# nuc977.net
KiCad netlist of a schematic drawn in Altium Designer
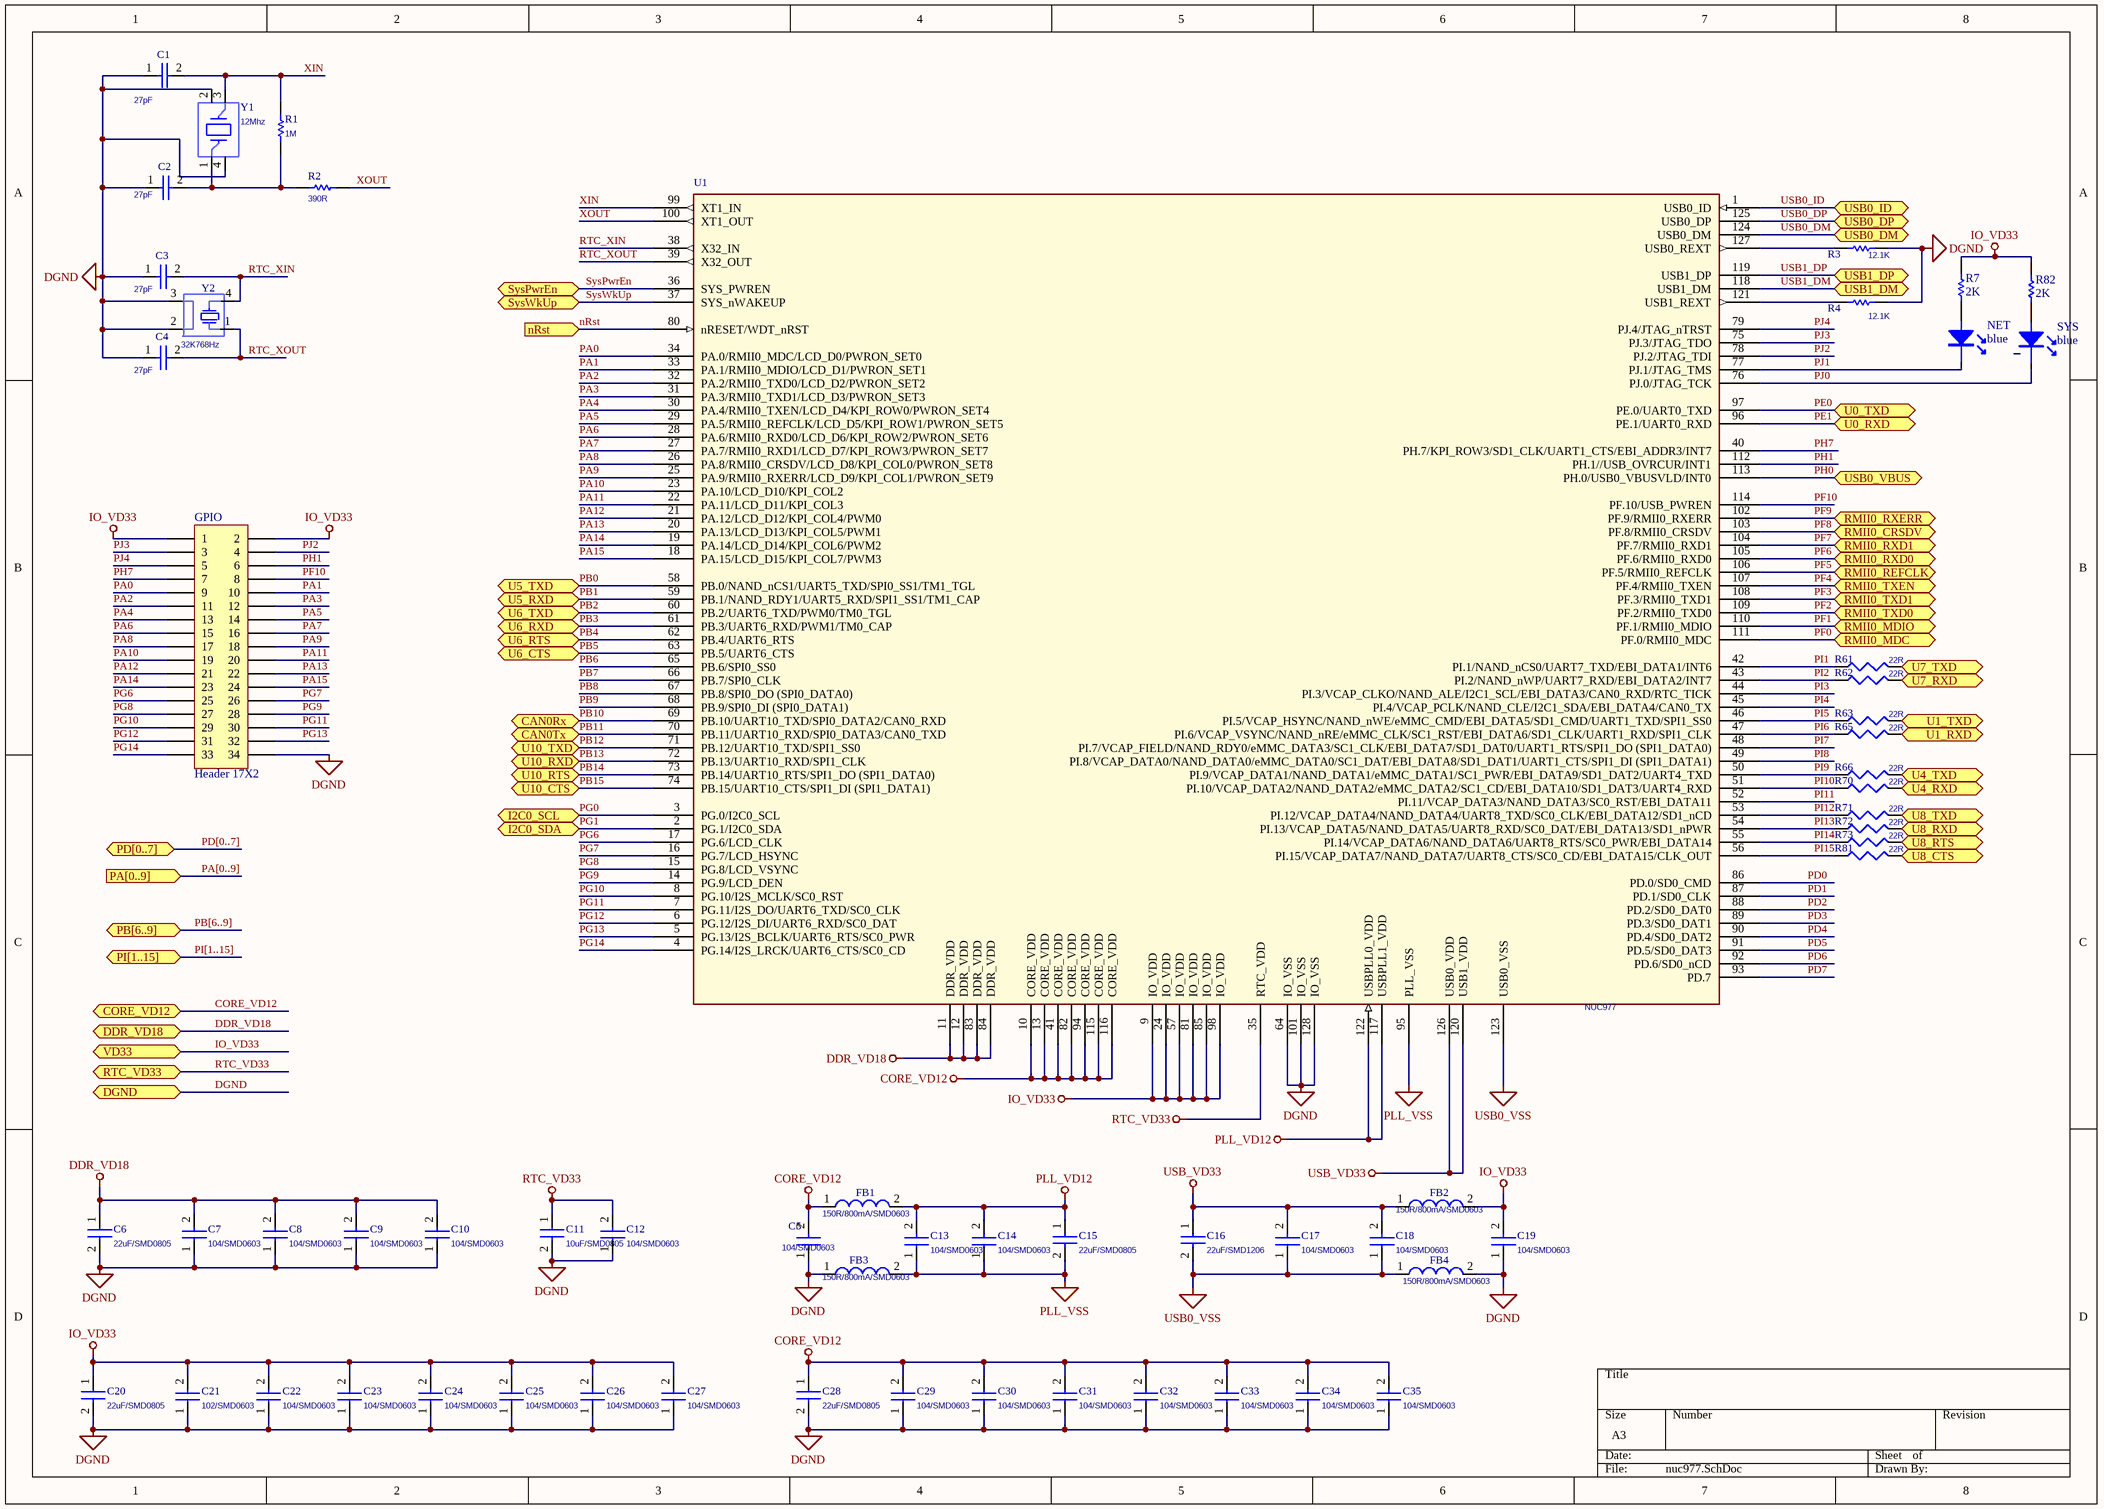
[diagram p0: nuc977.SchDoc]

(export (version "E")
  (design (tool "Eeschema 10.0.6"))
  (components
    (comp (ref "C1")
      (value "27pF")
      (footprint "0603C")
      (description "Capacitor")
      (libsource (lib "MYSTM32") (part "CAP"))
    )
    (comp (ref "C2")
      (value "27pF")
      (footprint "0603C")
      (description "Capacitor")
      (libsource (lib "MYSTM32") (part "CAP"))
    )
    (comp (ref "C3")
      (value "27pF")
      (footprint "0603C")
      (description "Capacitor")
      (libsource (lib "MYSTM32") (part "CAP"))
    )
    (comp (ref "C4")
      (value "27pF")
      (footprint "0603C")
      (description "Capacitor")
      (libsource (lib "MYSTM32") (part "CAP"))
    )
    (comp (ref "C5") (value "104/SMD0603") (footprint "0603C") (libsource (lib "*") (part "C/SMD0603")))
    (comp (ref "C6") (value "22uF/SMD0805") (footprint "C0805") (libsource (lib "*") (part "C/SMD1206")))
    (comp (ref "C7") (value "104/SMD0603") (footprint "0603C") (libsource (lib "*") (part "C/SMD0603")))
    (comp (ref "C8") (value "104/SMD0603") (footprint "0603C") (libsource (lib "*") (part "C/SMD0603")))
    (comp (ref "C9") (value "104/SMD0603") (footprint "0603C") (libsource (lib "*") (part "C/SMD0603")))
    (comp (ref "C10") (value "104/SMD0603") (footprint "0603C") (libsource (lib "*") (part "C/SMD0603")))
    (comp (ref "C11") (value "10uF/SMD0805") (footprint "C0805") (libsource (lib "*") (part "C/SMD0805")))
    (comp (ref "C12") (value "104/SMD0603") (footprint "0603C") (libsource (lib "*") (part "C/SMD0603")))
    (comp (ref "C13") (value "104/SMD0603") (footprint "0603C") (libsource (lib "*") (part "C/SMD0603")))
    (comp (ref "C14") (value "104/SMD0603") (footprint "0603C") (libsource (lib "*") (part "C/SMD0603")))
    (comp (ref "C15") (value "22uF/SMD0805") (footprint "C0805") (libsource (lib "*") (part "C/SMD1206")))
    (comp (ref "C16") (value "22uF/SMD1206") (footprint "C0805") (libsource (lib "*") (part "C/SMD1206")))
    (comp (ref "C17") (value "104/SMD0603") (footprint "0603C") (libsource (lib "*") (part "C/SMD0603")))
    (comp (ref "C18") (value "104/SMD0603") (footprint "0603C") (libsource (lib "*") (part "C/SMD0603")))
    (comp (ref "C19") (value "104/SMD0603") (footprint "0603C") (libsource (lib "*") (part "C/SMD0603")))
    (comp (ref "C20") (value "22uF/SMD0805") (footprint "C0805") (libsource (lib "*") (part "C/SMD1206")))
    (comp (ref "C21") (value "102/SMD0603") (footprint "0603C") (libsource (lib "*") (part "C/SMD0603")))
    (comp (ref "C22") (value "104/SMD0603") (footprint "0603C") (libsource (lib "*") (part "C/SMD0603")))
    (comp (ref "C23") (value "104/SMD0603") (footprint "0603C") (libsource (lib "*") (part "C/SMD0603")))
    (comp (ref "C24") (value "104/SMD0603") (footprint "0603C") (libsource (lib "*") (part "C/SMD0603")))
    (comp (ref "C25") (value "104/SMD0603") (footprint "0603C") (libsource (lib "*") (part "C/SMD0603")))
    (comp (ref "C26") (value "104/SMD0603") (footprint "0603C") (libsource (lib "*") (part "C/SMD0603")))
    (comp (ref "C27") (value "104/SMD0603") (footprint "0603C") (libsource (lib "*") (part "C/SMD0603")))
    (comp (ref "C28") (value "22uF/SMD0805") (footprint "C0805") (libsource (lib "*") (part "C/SMD1206")))
    (comp (ref "C29") (value "104/SMD0603") (footprint "0603C") (libsource (lib "*") (part "C/SMD0603")))
    (comp (ref "C30") (value "104/SMD0603") (footprint "0603C") (libsource (lib "*") (part "C/SMD0603")))
    (comp (ref "C31") (value "104/SMD0603") (footprint "0603C") (libsource (lib "*") (part "C/SMD0603")))
    (comp (ref "C32") (value "104/SMD0603") (footprint "0603C") (libsource (lib "*") (part "C/SMD0603")))
    (comp (ref "C33") (value "104/SMD0603") (footprint "0603C") (libsource (lib "*") (part "C/SMD0603")))
    (comp (ref "C34") (value "104/SMD0603") (footprint "0603C") (libsource (lib "*") (part "C/SMD0603")))
    (comp (ref "C35") (value "104/SMD0603") (footprint "0603C") (libsource (lib "*") (part "C/SMD0603")))
    (comp (ref "FB1")
      (value "150R/800mA/SMD0603")
      (footprint "0603R")
      (libsource (lib "*") (part "FB/SMD0603"))
    )
    (comp (ref "FB2")
      (value "150R/800mA/SMD0603")
      (footprint "0603R")
      (libsource (lib "*") (part "FB/SMD0603"))
    )
    (comp (ref "FB3")
      (value "150R/800mA/SMD0603")
      (footprint "0603R")
      (libsource (lib "*") (part "FB/SMD0603"))
    )
    (comp (ref "FB4")
      (value "150R/800mA/SMD0603")
      (footprint "0603R")
      (libsource (lib "*") (part "FB/SMD0603"))
    )
    (comp (ref "GPIO")
      (value "Header 17X2")
      (footprint "HDR2X17")
      (description "Header, 17-Pin, Dual row")
      (fields (field (name "PUBLISHER") "Altium Limited"))
      (libsource (lib "Miscellaneous Connectors") (part "Header 17X2"))
    )
    (comp (ref "NET") (value "blue") (footprint "LED-0603") (libsource (lib "GT2440原理图库") (part "LED")))
    (comp (ref "R1")
      (value "1M")
      (footprint "0603R")
      (description "Resistor")
      (fields (field (name "PUBLISHER") "Altium Limited"))
      (libsource (lib "STM32F107VCT") (part "res1"))
    )
    (comp (ref "R2")
      (value "390R")
      (footprint "0603R")
      (description "Resistor")
      (fields (field (name "PUBLISHER") "Altium Limited"))
      (libsource (lib "STM32F107VCT") (part "res1"))
    )
    (comp (ref "R3")
      (value "12.1K")
      (footprint "0603R")
      (description "Resistor")
      (fields (field (name "PUBLISHER") "Altium Limited"))
      (libsource (lib "STM32F107VCT") (part "res1"))
    )
    (comp (ref "R4")
      (value "12.1K")
      (footprint "0603R")
      (description "Resistor")
      (fields (field (name "PUBLISHER") "Altium Limited"))
      (libsource (lib "STM32F107VCT") (part "res1"))
    )
    (comp (ref "R7")
      (value "2K")
      (footprint "0603C")
      (description "Resistor")
      (fields (field (name "PUBLISHER") "Altium Limited"))
      (libsource (lib "Miscellaneous Devices") (part "res1"))
    )
    (comp (ref "R61") (value "22R") (footprint "0603R") (libsource (lib "*") (part "R_Dup1")))
    (comp (ref "R62") (value "22R") (footprint "0603R") (libsource (lib "*") (part "R_Dup1")))
    (comp (ref "R63") (value "22R") (footprint "0603R") (libsource (lib "*") (part "R_Dup1")))
    (comp (ref "R65") (value "22R") (footprint "0603R") (libsource (lib "*") (part "R_Dup1")))
    (comp (ref "R66") (value "22R") (footprint "0603R") (libsource (lib "*") (part "R_Dup1")))
    (comp (ref "R70") (value "22R") (footprint "0603R") (libsource (lib "*") (part "R_Dup1")))
    (comp (ref "R71") (value "22R") (footprint "0603R") (libsource (lib "*") (part "R_Dup1")))
    (comp (ref "R72") (value "22R") (footprint "0603R") (libsource (lib "*") (part "R_Dup1")))
    (comp (ref "R73") (value "22R") (footprint "0603R") (libsource (lib "*") (part "R_Dup1")))
    (comp (ref "R81") (value "22R") (footprint "0603R") (libsource (lib "*") (part "R_Dup1")))
    (comp (ref "R82")
      (value "2K")
      (footprint "0603C")
      (description "Resistor")
      (fields (field (name "PUBLISHER") "Altium Limited"))
      (libsource (lib "Miscellaneous Devices") (part "res1"))
    )
    (comp (ref "SYS") (value "blue") (footprint "LED-0603") (libsource (lib "GT2440原理图库") (part "LED")))
    (comp (ref "U1") (value "NUC977") (footprint "QFP128/16/0.4") (libsource (lib "*") (part "NUC977_7")))
    (comp (ref "Y1") (value "12Mhz") (footprint "HCX-3SB3225") (libsource (lib "changyong") (part "12Mhz")))
    (comp (ref "Y2") (value "32K768Hz") (footprint "32K768Hz") (libsource (lib "n32905") (part "32K768Hz")))
  )
  (nets
    (net (code "1") (name "/PA0") (class "Default")
      (node (ref "GPIO") (pin "9") (pinfunction "9_9") (pintype "passive"))
      (node (ref "U1") (pin "34") (pinfunction "PA.0/RMII0_MDC/LCD_D0/PWRON_SET0_34") (pintype "passive"))
    )
    (net (code "2") (name "/PA1") (class "Default")
      (node (ref "GPIO") (pin "10") (pinfunction "10_10") (pintype "passive"))
      (node (ref "U1") (pin "33") (pinfunction "PA.1/RMII0_MDIO/LCD_D1/PWRON_SET1_33") (pintype "passive"))
    )
    (net (code "3") (name "/PA2") (class "Default")
      (node (ref "GPIO") (pin "11") (pinfunction "11_11") (pintype "passive"))
      (node (ref "U1") (pin "32") (pinfunction "PA.2/RMII0_TXD0/LCD_D2/PWRON_SET2_32") (pintype "passive"))
    )
    (net (code "4") (name "/PA3") (class "Default")
      (node (ref "GPIO") (pin "12") (pinfunction "12_12") (pintype "passive"))
      (node (ref "U1") (pin "31") (pinfunction "PA.3/RMII0_TXD1/LCD_D3/PWRON_SET3_31") (pintype "passive"))
    )
    (net (code "5") (name "/PA4") (class "Default")
      (node (ref "GPIO") (pin "13") (pinfunction "13_13") (pintype "passive"))
      (node (ref "U1") (pin "30") (pinfunction "PA.4/RMII0_TXEN/LCD_D4/KPI_ROW0/PWRON_SET4_30") (pintype "passive"))
    )
    (net (code "6") (name "/PA5") (class "Default")
      (node (ref "GPIO") (pin "14") (pinfunction "14_14") (pintype "passive"))
      (node (ref "U1") (pin "29") (pinfunction "PA.5/RMII0_REFCLK/LCD_D5/KPI_ROW1/PWRON_SET5_29") (pintype "passive"))
    )
    (net (code "7") (name "/PA6") (class "Default")
      (node (ref "GPIO") (pin "15") (pinfunction "15_15") (pintype "passive"))
      (node (ref "U1") (pin "28") (pinfunction "PA.6/RMII0_RXD0/LCD_D6/KPI_ROW2/PWRON_SET6_28") (pintype "passive"))
    )
    (net (code "8") (name "/PA7") (class "Default")
      (node (ref "GPIO") (pin "16") (pinfunction "16_16") (pintype "passive"))
      (node (ref "U1") (pin "27") (pinfunction "PA.7/RMII0_RXD1/LCD_D7/KPI_ROW3/PWRON_SET7_27") (pintype "passive"))
    )
    (net (code "9") (name "/PA8") (class "Default")
      (node (ref "GPIO") (pin "17") (pinfunction "17_17") (pintype "passive"))
      (node (ref "U1") (pin "26") (pinfunction "PA.8/RMII0_CRSDV/LCD_D8/KPI_COL0/PWRON_SET8_26") (pintype "passive"))
    )
    (net (code "10") (name "/PA9") (class "Default")
      (node (ref "GPIO") (pin "18") (pinfunction "18_18") (pintype "passive"))
      (node (ref "U1") (pin "25") (pinfunction "PA.9/RMII0_RXERR/LCD_D9/KPI_COL1/PWRON_SET9_25") (pintype "passive"))
    )
    (net (code "11") (name "/PA10") (class "Default")
      (node (ref "GPIO") (pin "19") (pinfunction "19_19") (pintype "passive"))
      (node (ref "U1") (pin "23") (pinfunction "PA.10/LCD_D10/KPI_COL2_23") (pintype "passive"))
    )
    (net (code "12") (name "/PA11") (class "Default")
      (node (ref "GPIO") (pin "20") (pinfunction "20_20") (pintype "passive"))
      (node (ref "U1") (pin "22") (pinfunction "PA.11/LCD_D11/KPI_COL3_22") (pintype "passive"))
    )
    (net (code "13") (name "/PA12") (class "Default")
      (node (ref "GPIO") (pin "21") (pinfunction "21_21") (pintype "passive"))
      (node (ref "U1") (pin "21") (pinfunction "PA.12/LCD_D12/KPI_COL4/PWM0_21") (pintype "passive"))
    )
    (net (code "14") (name "/PA13") (class "Default")
      (node (ref "GPIO") (pin "22") (pinfunction "22_22") (pintype "passive"))
      (node (ref "U1") (pin "20") (pinfunction "PA.13/LCD_D13/KPI_COL5/PWM1_20") (pintype "passive"))
    )
    (net (code "15") (name "/PA14") (class "Default")
      (node (ref "GPIO") (pin "23") (pinfunction "23_23") (pintype "passive"))
      (node (ref "U1") (pin "19") (pinfunction "PA.14/LCD_D14/KPI_COL6/PWM2_19") (pintype "passive"))
    )
    (net (code "16") (name "/PA15") (class "Default")
      (node (ref "GPIO") (pin "24") (pinfunction "24_24") (pintype "passive"))
      (node (ref "U1") (pin "18") (pinfunction "PA.15/LCD_D15/KPI_COL7/PWM3_18") (pintype "passive"))
    )
    (net (code "18") (name "/PB0") (class "Default")
      (node (ref "U1") (pin "58") (pinfunction "PB.0/NAND_nCS1/UART5_TXD/SPI0_SS1/TM1_TGL_58") (pintype "passive"))
    )
    (net (code "19") (name "/PB1") (class "Default")
      (node (ref "U1") (pin "59") (pinfunction "PB.1/NAND_RDY1/UART5_RXD/SPI1_SS1/TM1_CAP_59") (pintype "passive"))
    )
    (net (code "20") (name "/PB2") (class "Default")
      (node (ref "U1") (pin "60") (pinfunction "PB.2/UART6_TXD/PWM0/TM0_TGL_60") (pintype "passive"))
    )
    (net (code "21") (name "/PB3") (class "Default")
      (node (ref "U1") (pin "61") (pinfunction "PB.3/UART6_RXD/PWM1/TM0_CAP_61") (pintype "passive"))
    )
    (net (code "22") (name "/PB4") (class "Default")
      (node (ref "U1") (pin "62") (pinfunction "PB.4/UART6_RTS_62") (pintype "passive"))
    )
    (net (code "23") (name "/PB5") (class "Default")
      (node (ref "U1") (pin "63") (pinfunction "PB.5/UART6_CTS_63") (pintype "passive"))
    )
    (net (code "24") (name "/PB6") (class "Default")
      (node (ref "U1") (pin "65") (pinfunction "PB.6/SPI0_SS0_65") (pintype "passive"))
    )
    (net (code "25") (name "/PB7") (class "Default")
      (node (ref "U1") (pin "66") (pinfunction "PB.7/SPI0_CLK_66") (pintype "passive"))
    )
    (net (code "26") (name "/PB8") (class "Default")
      (node (ref "U1") (pin "67") (pinfunction "PB.8/SPI0_DO_(SPI0_DATA0)_67") (pintype "passive"))
    )
    (net (code "27") (name "/PB9") (class "Default")
      (node (ref "U1") (pin "68") (pinfunction "PB.9/SPI0_DI_(SPI0_DATA1)_68") (pintype "passive"))
    )
    (net (code "28") (name "/PB10") (class "Default")
      (node (ref "U1") (pin "69") (pinfunction "PB.10/UART10_TXD/SPI0_DATA2/CAN0_RXD_69") (pintype "passive"))
    )
    (net (code "29") (name "/PB11") (class "Default")
      (node (ref "U1") (pin "70") (pinfunction "PB.11/UART10_RXD/SPI0_DATA3/CAN0_TXD_70") (pintype "passive"))
    )
    (net (code "30") (name "/PB12") (class "Default")
      (node (ref "U1") (pin "71") (pinfunction "PB.12/UART10_TXD/SPI1_SS0_71") (pintype "passive"))
    )
    (net (code "31") (name "/PB13") (class "Default")
      (node (ref "U1") (pin "72") (pinfunction "PB.13/UART10_RXD/SPI1_CLK_72") (pintype "passive"))
    )
    (net (code "32") (name "/PB14") (class "Default")
      (node (ref "U1") (pin "73") (pinfunction "PB.14/UART10_RTS/SPI1_DO_(SPI1_DATA0)_73") (pintype "passive"))
    )
    (net (code "33") (name "/PB15") (class "Default")
      (node (ref "U1") (pin "74") (pinfunction "PB.15/UART10_CTS/SPI1_DI_(SPI1_DATA1)_74") (pintype "passive"))
    )
    (net (code "35") (name "/PD0") (class "Default")
      (node (ref "U1") (pin "86") (pinfunction "PD.0/SD0_CMD_86") (pintype "passive"))
    )
    (net (code "36") (name "/PD1") (class "Default")
      (node (ref "U1") (pin "87") (pinfunction "PD.1/SD0_CLK_87") (pintype "passive"))
    )
    (net (code "37") (name "/PD2") (class "Default")
      (node (ref "U1") (pin "88") (pinfunction "PD.2/SD0_DAT0_88") (pintype "passive"))
    )
    (net (code "38") (name "/PD3") (class "Default")
      (node (ref "U1") (pin "89") (pinfunction "PD.3/SD0_DAT1_89") (pintype "passive"))
    )
    (net (code "39") (name "/PD4") (class "Default")
      (node (ref "U1") (pin "90") (pinfunction "PD.4/SD0_DAT2_90") (pintype "passive"))
    )
    (net (code "40") (name "/PD5") (class "Default")
      (node (ref "U1") (pin "91") (pinfunction "PD.5/SD0_DAT3_91") (pintype "passive"))
    )
    (net (code "41") (name "/PD6") (class "Default")
      (node (ref "U1") (pin "92") (pinfunction "PD.6/SD0_nCD_92") (pintype "passive"))
    )
    (net (code "42") (name "/PD7") (class "Default")
      (node (ref "U1") (pin "93") (pinfunction "PD.7_93") (pintype "passive"))
    )
    (net (code "44") (name "/PE0") (class "Default")
      (node (ref "U1") (pin "97") (pinfunction "PE.0/UART0_TXD_97") (pintype "passive"))
    )
    (net (code "45") (name "/PE1") (class "Default")
      (node (ref "U1") (pin "96") (pinfunction "PE.1/UART0_RXD_96") (pintype "passive"))
    )
    (net (code "46") (name "/PF0") (class "Default")
      (node (ref "U1") (pin "111") (pinfunction "PF.0/RMII0_MDC_111") (pintype "passive"))
    )
    (net (code "47") (name "/PF1") (class "Default")
      (node (ref "U1") (pin "110") (pinfunction "PF.1/RMII0_MDIO_110") (pintype "passive"))
    )
    (net (code "48") (name "/PF2") (class "Default")
      (node (ref "U1") (pin "109") (pinfunction "PF.2/RMII0_TXD0_109") (pintype "passive"))
    )
    (net (code "49") (name "/PF3") (class "Default")
      (node (ref "U1") (pin "108") (pinfunction "PF.3/RMII0_TXD1_108") (pintype "passive"))
    )
    (net (code "50") (name "/PF4") (class "Default")
      (node (ref "U1") (pin "107") (pinfunction "PF.4/RMII0_TXEN_107") (pintype "passive"))
    )
    (net (code "51") (name "/PF5") (class "Default")
      (node (ref "U1") (pin "106") (pinfunction "PF.5/RMII0_REFCLK_106") (pintype "passive"))
    )
    (net (code "52") (name "/PF6") (class "Default")
      (node (ref "U1") (pin "105") (pinfunction "PF.6/RMII0_RXD0_105") (pintype "passive"))
    )
    (net (code "53") (name "/PF7") (class "Default")
      (node (ref "U1") (pin "104") (pinfunction "PF.7/RMII0_RXD1_104") (pintype "passive"))
    )
    (net (code "54") (name "/PF8") (class "Default")
      (node (ref "U1") (pin "103") (pinfunction "PF.8/RMII0_CRSDV_103") (pintype "passive"))
    )
    (net (code "55") (name "/PF9") (class "Default")
      (node (ref "U1") (pin "102") (pinfunction "PF.9/RMII0_RXERR_102") (pintype "passive"))
    )
    (net (code "56") (name "/PF10") (class "Default")
      (node (ref "GPIO") (pin "8") (pinfunction "8_8") (pintype "passive"))
      (node (ref "U1") (pin "114") (pinfunction "PF.10/USB_PWREN_114") (pintype "passive"))
    )
    (net (code "57") (name "/PG0") (class "Default")
      (node (ref "U1") (pin "3") (pinfunction "PG.0/I2C0_SCL_3") (pintype "passive"))
    )
    (net (code "58") (name "/PG1") (class "Default")
      (node (ref "U1") (pin "2") (pinfunction "PG.1/I2C0_SDA_2") (pintype "passive"))
    )
    (net (code "59") (name "/PG6") (class "Default")
      (node (ref "GPIO") (pin "25") (pinfunction "25_25") (pintype "passive"))
      (node (ref "U1") (pin "17") (pinfunction "PG.6/LCD_CLK_17") (pintype "passive"))
    )
    (net (code "60") (name "/PG7") (class "Default")
      (node (ref "GPIO") (pin "26") (pinfunction "26_26") (pintype "passive"))
      (node (ref "U1") (pin "16") (pinfunction "PG.7/LCD_HSYNC_16") (pintype "passive"))
    )
    (net (code "61") (name "/PG8") (class "Default")
      (node (ref "GPIO") (pin "27") (pinfunction "27_27") (pintype "passive"))
      (node (ref "U1") (pin "15") (pinfunction "PG.8/LCD_VSYNC_15") (pintype "passive"))
    )
    (net (code "62") (name "/PG9") (class "Default")
      (node (ref "GPIO") (pin "28") (pinfunction "28_28") (pintype "passive"))
      (node (ref "U1") (pin "14") (pinfunction "PG.9/LCD_DEN_14") (pintype "passive"))
    )
    (net (code "63") (name "/PG10") (class "Default")
      (node (ref "GPIO") (pin "29") (pinfunction "29_29") (pintype "passive"))
      (node (ref "U1") (pin "8") (pinfunction "PG.10/I2S_MCLK/SC0_RST_8") (pintype "passive"))
    )
    (net (code "64") (name "/PG11") (class "Default")
      (node (ref "GPIO") (pin "30") (pinfunction "30_30") (pintype "passive"))
      (node (ref "U1") (pin "7") (pinfunction "PG.11/I2S_DO/UART6_TXD/SC0_CLK_7") (pintype "passive"))
    )
    (net (code "65") (name "/PG12") (class "Default")
      (node (ref "GPIO") (pin "31") (pinfunction "31_31") (pintype "passive"))
      (node (ref "U1") (pin "6") (pinfunction "PG.12/I2S_DI/UART6_RXD/SC0_DAT_6") (pintype "passive"))
    )
    (net (code "66") (name "/PG13") (class "Default")
      (node (ref "GPIO") (pin "32") (pinfunction "32_32") (pintype "passive"))
      (node (ref "U1") (pin "5") (pinfunction "PG.13/I2S_BCLK/UART6_RTS/SC0_PWR_5") (pintype "passive"))
    )
    (net (code "67") (name "/PG14") (class "Default")
      (node (ref "GPIO") (pin "33") (pinfunction "33_33") (pintype "passive"))
      (node (ref "U1") (pin "4") (pinfunction "PG.14/I2S_LRCK/UART6_CTS/SC0_CD_4") (pintype "passive"))
    )
    (net (code "68") (name "/PH0") (class "Default")
      (node (ref "U1") (pin "113") (pinfunction "PH.0/USB0_VBUSVLD/INT0_113") (pintype "passive"))
    )
    (net (code "69") (name "/PH1") (class "Default")
      (node (ref "GPIO") (pin "6") (pinfunction "6_6") (pintype "passive"))
      (node (ref "U1") (pin "112") (pinfunction "PH.1//USB_OVRCUR/INT1_112") (pintype "passive"))
    )
    (net (code "70") (name "/PH7") (class "Default")
      (node (ref "GPIO") (pin "7") (pinfunction "7_7") (pintype "passive"))
      (node (ref "U1") (pin "40") (pinfunction "PH.7/KPI_ROW3/SD1_CLK/UART1_CTS/EBI_ADDR3/INT7_40") (pintype "passive"))
    )
    (net (code "71") (name "/PI1") (class "Default")
      (node (ref "R61") (pin "1") (pinfunction "1_1") (pintype "passive"))
      (node (ref "U1") (pin "42") (pinfunction "PI.1/NAND_nCS0/UART7_TXD/EBI_DATA1/INT6_42") (pintype "passive"))
    )
    (net (code "72") (name "/PI2") (class "Default")
      (node (ref "R62") (pin "1") (pinfunction "1_1") (pintype "passive"))
      (node (ref "U1") (pin "43") (pinfunction "PI.2/NAND_nWP/UART7_RXD/EBI_DATA2/INT7_43") (pintype "passive"))
    )
    (net (code "73") (name "/PI3") (class "Default")
      (node (ref "U1") (pin "44") (pinfunction "PI.3/VCAP_CLKO/NAND_ALE/I2C1_SCL/EBI_DATA3/CAN0_RXD/RTC_TICK_44") (pintype "passive"))
    )
    (net (code "74") (name "/PI4") (class "Default")
      (node (ref "U1") (pin "45") (pinfunction "PI.4/VCAP_PCLK/NAND_CLE/I2C1_SDA/EBI_DATA4/CAN0_TX_45") (pintype "passive"))
    )
    (net (code "75") (name "/PI5") (class "Default")
      (node (ref "R63") (pin "1") (pinfunction "1_1") (pintype "passive"))
      (node (ref "U1") (pin "46") (pinfunction "PI.5/VCAP_HSYNC/NAND_nWE/eMMC_CMD/EBI_DATA5/SD1_CMD/UART1_TXD/SPI1_SS0_46") (pintype "passive"))
    )
    (net (code "76") (name "/PI6") (class "Default")
      (node (ref "R65") (pin "1") (pinfunction "1_1") (pintype "passive"))
      (node (ref "U1") (pin "47") (pinfunction "PI.6/VCAP_VSYNC/NAND_nRE/eMMC_CLK/SC1_RST/EBI_DATA6/SD1_CLK/UART1_RXD/SPI1_CLK_47") (pintype "passive"))
    )
    (net (code "77") (name "/PI7") (class "Default")
      (node (ref "U1") (pin "48") (pinfunction "PI.7/VCAP_FIELD/NAND_RDY0/eMMC_DATA3/SC1_CLK/EBI_DATA7/SD1_DAT0/UART1_RTS/SPI1_DO_(SPI1_DATA0)_48") (pintype "passive"))
    )
    (net (code "78") (name "/PI8") (class "Default")
      (node (ref "U1") (pin "49") (pinfunction "PI.8/VCAP_DATA0/NAND_DATA0/eMMC_DATA0/SC1_DAT/EBI_DATA8/SD1_DAT1/UART1_CTS/SPI1_DI_(SPI1_DATA1)_49") (pintype "passive"))
    )
    (net (code "79") (name "/PI9") (class "Default")
      (node (ref "R66") (pin "1") (pinfunction "1_1") (pintype "passive"))
      (node (ref "U1") (pin "50") (pinfunction "PI.9/VCAP_DATA1/NAND_DATA1/eMMC_DATA1/SC1_PWR/EBI_DATA9/SD1_DAT2/UART4_TXD_50") (pintype "passive"))
    )
    (net (code "80") (name "/PI10") (class "Default")
      (node (ref "R70") (pin "1") (pinfunction "1_1") (pintype "passive"))
      (node (ref "U1") (pin "51") (pinfunction "PI.10/VCAP_DATA2/NAND_DATA2/eMMC_DATA2/SC1_CD/EBI_DATA10/SD1_DAT3/UART4_RXD_51") (pintype "passive"))
    )
    (net (code "81") (name "/PI11") (class "Default")
      (node (ref "U1") (pin "52") (pinfunction "PI.11/VCAP_DATA3/NAND_DATA3/SC0_RST/EBI_DATA11_52") (pintype "passive"))
    )
    (net (code "82") (name "/PI12") (class "Default")
      (node (ref "R71") (pin "1") (pinfunction "1_1") (pintype "passive"))
      (node (ref "U1") (pin "53") (pinfunction "PI.12/VCAP_DATA4/NAND_DATA4/UART8_TXD/SC0_CLK/EBI_DATA12/SD1_nCD_53") (pintype "passive"))
    )
    (net (code "83") (name "/PI13") (class "Default")
      (node (ref "R72") (pin "1") (pinfunction "1_1") (pintype "passive"))
      (node (ref "U1") (pin "54") (pinfunction "PI.13/VCAP_DATA5/NAND_DATA5/UART8_RXD/SC0_DAT/EBI_DATA13/SD1_nPWR_54") (pintype "passive"))
    )
    (net (code "84") (name "/PI14") (class "Default")
      (node (ref "R73") (pin "1") (pinfunction "1_1") (pintype "passive"))
      (node (ref "U1") (pin "55") (pinfunction "PI.14/VCAP_DATA6/NAND_DATA6/UART8_RTS/SC0_PWR/EBI_DATA14_55") (pintype "passive"))
    )
    (net (code "85") (name "/PI15") (class "Default")
      (node (ref "R81") (pin "1") (pinfunction "1_1") (pintype "passive"))
      (node (ref "U1") (pin "56") (pinfunction "PI.15/VCAP_DATA7/NAND_DATA7/UART8_CTS/SC0_CD/EBI_DATA15/CLK_OUT_56") (pintype "passive"))
    )
    (net (code "87") (name "/PJ0") (class "Default")
      (node (ref "SYS") (pin "2") (pinfunction "2_2") (pintype "passive"))
      (node (ref "U1") (pin "76") (pinfunction "PJ.0/JTAG_TCK_76") (pintype "passive"))
    )
    (net (code "88") (name "/PJ1") (class "Default")
      (node (ref "NET") (pin "2") (pinfunction "2_2") (pintype "passive"))
      (node (ref "U1") (pin "77") (pinfunction "PJ.1/JTAG_TMS_77") (pintype "passive"))
    )
    (net (code "89") (name "/PJ2") (class "Default")
      (node (ref "GPIO") (pin "4") (pinfunction "4_4") (pintype "passive"))
      (node (ref "U1") (pin "78") (pinfunction "PJ.2/JTAG_TDI_78") (pintype "passive"))
    )
    (net (code "90") (name "/PJ3") (class "Default")
      (node (ref "GPIO") (pin "3") (pinfunction "3_3") (pintype "passive"))
      (node (ref "U1") (pin "75") (pinfunction "PJ.3/JTAG_TDO_75") (pintype "passive"))
    )
    (net (code "91") (name "/PJ4") (class "Default")
      (node (ref "GPIO") (pin "5") (pinfunction "5_5") (pintype "passive"))
      (node (ref "U1") (pin "79") (pinfunction "PJ.4/JTAG_nTRST_79") (pintype "passive"))
    )
    (net (code "92") (name "/RTC_XIN") (class "Default")
      (node (ref "C3") (pin "2") (pinfunction "2_2") (pintype "passive"))
      (node (ref "U1") (pin "38") (pinfunction "X32_IN_38") (pintype "output"))
      (node (ref "Y2") (pin "4") (pinfunction "4_4") (pintype "passive"))
    )
    (net (code "93") (name "/RTC_XOUT") (class "Default")
      (node (ref "C4") (pin "2") (pinfunction "2_2") (pintype "passive"))
      (node (ref "U1") (pin "39") (pinfunction "X32_OUT_39") (pintype "output"))
      (node (ref "Y2") (pin "1") (pinfunction "1_1") (pintype "passive"))
    )
    (net (code "94") (name "/SysPwrEn") (class "Default")
      (node (ref "U1") (pin "36") (pinfunction "SYS_PWREN_36") (pintype "passive"))
    )
    (net (code "95") (name "/SysWkUp") (class "Default")
      (node (ref "U1") (pin "37") (pinfunction "SYS_nWAKEUP_37") (pintype "passive"))
    )
    (net (code "96") (name "/U1_RXD") (class "Default")
      (node (ref "R65") (pin "2") (pinfunction "2_2") (pintype "passive"))
    )
    (net (code "97") (name "/U1_TXD") (class "Default")
      (node (ref "R63") (pin "2") (pinfunction "2_2") (pintype "passive"))
    )
    (net (code "98") (name "/U4_RXD") (class "Default")
      (node (ref "R70") (pin "2") (pinfunction "2_2") (pintype "passive"))
    )
    (net (code "99") (name "/U4_TXD") (class "Default")
      (node (ref "R66") (pin "2") (pinfunction "2_2") (pintype "passive"))
    )
    (net (code "100") (name "/U7_RXD") (class "Default")
      (node (ref "R62") (pin "2") (pinfunction "2_2") (pintype "passive"))
    )
    (net (code "101") (name "/U7_TXD") (class "Default")
      (node (ref "R61") (pin "2") (pinfunction "2_2") (pintype "passive"))
    )
    (net (code "102") (name "/U8_CTS") (class "Default")
      (node (ref "R81") (pin "2") (pinfunction "2_2") (pintype "passive"))
    )
    (net (code "103") (name "/U8_RTS") (class "Default")
      (node (ref "R73") (pin "2") (pinfunction "2_2") (pintype "passive"))
    )
    (net (code "104") (name "/U8_RXD") (class "Default")
      (node (ref "R72") (pin "2") (pinfunction "2_2") (pintype "passive"))
    )
    (net (code "105") (name "/U8_TXD") (class "Default")
      (node (ref "R71") (pin "2") (pinfunction "2_2") (pintype "passive"))
    )
    (net (code "106") (name "/USB0_DM") (class "Default")
      (node (ref "U1") (pin "124") (pinfunction "USB0_DM_124") (pintype "passive"))
    )
    (net (code "107") (name "/USB0_DP") (class "Default")
      (node (ref "U1") (pin "125") (pinfunction "USB0_DP_125") (pintype "passive"))
    )
    (net (code "108") (name "/USB0_ID") (class "Default")
      (node (ref "U1") (pin "1") (pinfunction "USB0_ID_1") (pintype "input"))
    )
    (net (code "109") (name "/USB1_DM") (class "Default")
      (node (ref "U1") (pin "118") (pinfunction "USB1_DM_118") (pintype "passive"))
    )
    (net (code "110") (name "/USB1_DP") (class "Default")
      (node (ref "U1") (pin "119") (pinfunction "USB1_DP_119") (pintype "passive"))
    )
    (net (code "111") (name "/XIN") (class "Default")
      (node (ref "C1") (pin "2") (pinfunction "2_2") (pintype "passive"))
      (node (ref "R1") (pin "1") (pinfunction "1_1") (pintype "passive"))
      (node (ref "U1") (pin "99") (pinfunction "XT1_IN_99") (pintype "output"))
      (node (ref "Y1") (pin "3") (pinfunction "3_3") (pintype "passive"))
    )
    (net (code "112") (name "/XOUT") (class "Default")
      (node (ref "R2") (pin "2") (pinfunction "2_2") (pintype "passive"))
      (node (ref "U1") (pin "100") (pinfunction "XT1_OUT_100") (pintype "output"))
    )
    (net (code "113") (name "/nRst") (class "Default")
      (node (ref "U1") (pin "80") (pinfunction "nRESET/WDT_nRST_80") (pintype "input"))
    )
    (net (code "114") (name "CORE_VD12") (class "Default")
      (node (ref "C28") (pin "1") (pinfunction "1_1") (pintype "passive"))
      (node (ref "C29") (pin "2") (pinfunction "2_2") (pintype "passive"))
      (node (ref "C30") (pin "2") (pinfunction "2_2") (pintype "passive"))
      (node (ref "C31") (pin "2") (pinfunction "2_2") (pintype "passive"))
      (node (ref "C32") (pin "2") (pinfunction "2_2") (pintype "passive"))
      (node (ref "C33") (pin "2") (pinfunction "2_2") (pintype "passive"))
      (node (ref "C34") (pin "2") (pinfunction "2_2") (pintype "passive"))
      (node (ref "C35") (pin "2") (pinfunction "2_2") (pintype "passive"))
      (node (ref "C5") (pin "2") (pinfunction "2_2") (pintype "passive"))
      (node (ref "FB1") (pin "1") (pinfunction "1_1") (pintype "passive"))
      (node (ref "U1") (pin "10") (pinfunction "CORE_VDD_10") (pintype "power_in"))
      (node (ref "U1") (pin "115") (pinfunction "CORE_VDD_115") (pintype "power_in"))
      (node (ref "U1") (pin "116") (pinfunction "CORE_VDD_116") (pintype "power_in"))
      (node (ref "U1") (pin "13") (pinfunction "CORE_VDD_13") (pintype "power_in"))
      (node (ref "U1") (pin "41") (pinfunction "CORE_VDD_41") (pintype "power_in"))
      (node (ref "U1") (pin "82") (pinfunction "CORE_VDD_82") (pintype "power_in"))
      (node (ref "U1") (pin "94") (pinfunction "CORE_VDD_94") (pintype "power_in"))
    )
    (net (code "115") (name "DDR_VD18") (class "Default")
      (node (ref "C10") (pin "2") (pinfunction "2_2") (pintype "passive"))
      (node (ref "C6") (pin "1") (pinfunction "1_1") (pintype "passive"))
      (node (ref "C7") (pin "2") (pinfunction "2_2") (pintype "passive"))
      (node (ref "C8") (pin "2") (pinfunction "2_2") (pintype "passive"))
      (node (ref "C9") (pin "2") (pinfunction "2_2") (pintype "passive"))
      (node (ref "U1") (pin "11") (pinfunction "DDR_VDD_11") (pintype "power_in"))
      (node (ref "U1") (pin "12") (pinfunction "DDR_VDD_12") (pintype "power_in"))
      (node (ref "U1") (pin "83") (pinfunction "DDR_VDD_83") (pintype "power_in"))
      (node (ref "U1") (pin "84") (pinfunction "DDR_VDD_84") (pintype "power_in"))
    )
    (net (code "116") (name "DGND") (class "Default")
      (node (ref "C1") (pin "1") (pinfunction "1_1") (pintype "passive"))
      (node (ref "C10") (pin "1") (pinfunction "1_1") (pintype "passive"))
      (node (ref "C11") (pin "2") (pinfunction "2_2") (pintype "passive"))
      (node (ref "C12") (pin "1") (pinfunction "1_1") (pintype "passive"))
      (node (ref "C19") (pin "1") (pinfunction "1_1") (pintype "passive"))
      (node (ref "C2") (pin "1") (pinfunction "1_1") (pintype "passive"))
      (node (ref "C20") (pin "2") (pinfunction "2_2") (pintype "passive"))
      (node (ref "C21") (pin "1") (pinfunction "1_1") (pintype "passive"))
      (node (ref "C22") (pin "1") (pinfunction "1_1") (pintype "passive"))
      (node (ref "C23") (pin "1") (pinfunction "1_1") (pintype "passive"))
      (node (ref "C24") (pin "1") (pinfunction "1_1") (pintype "passive"))
      (node (ref "C25") (pin "1") (pinfunction "1_1") (pintype "passive"))
      (node (ref "C26") (pin "1") (pinfunction "1_1") (pintype "passive"))
      (node (ref "C27") (pin "1") (pinfunction "1_1") (pintype "passive"))
      (node (ref "C28") (pin "2") (pinfunction "2_2") (pintype "passive"))
      (node (ref "C29") (pin "1") (pinfunction "1_1") (pintype "passive"))
      (node (ref "C3") (pin "1") (pinfunction "1_1") (pintype "passive"))
      (node (ref "C30") (pin "1") (pinfunction "1_1") (pintype "passive"))
      (node (ref "C31") (pin "1") (pinfunction "1_1") (pintype "passive"))
      (node (ref "C32") (pin "1") (pinfunction "1_1") (pintype "passive"))
      (node (ref "C33") (pin "1") (pinfunction "1_1") (pintype "passive"))
      (node (ref "C34") (pin "1") (pinfunction "1_1") (pintype "passive"))
      (node (ref "C35") (pin "1") (pinfunction "1_1") (pintype "passive"))
      (node (ref "C4") (pin "1") (pinfunction "1_1") (pintype "passive"))
      (node (ref "C5") (pin "1") (pinfunction "1_1") (pintype "passive"))
      (node (ref "C6") (pin "2") (pinfunction "2_2") (pintype "passive"))
      (node (ref "C7") (pin "1") (pinfunction "1_1") (pintype "passive"))
      (node (ref "C8") (pin "1") (pinfunction "1_1") (pintype "passive"))
      (node (ref "C9") (pin "1") (pinfunction "1_1") (pintype "passive"))
      (node (ref "FB3") (pin "1") (pinfunction "1_1") (pintype "passive"))
      (node (ref "FB4") (pin "2") (pinfunction "2_2") (pintype "passive"))
      (node (ref "GPIO") (pin "34") (pinfunction "34_34") (pintype "passive"))
      (node (ref "R3") (pin "2") (pinfunction "2_2") (pintype "passive"))
      (node (ref "R4") (pin "2") (pinfunction "2_2") (pintype "passive"))
      (node (ref "U1") (pin "101") (pinfunction "IO_VSS_101") (pintype "power_in"))
      (node (ref "U1") (pin "128") (pinfunction "IO_VSS_128") (pintype "power_in"))
      (node (ref "U1") (pin "64") (pinfunction "IO_VSS_64") (pintype "power_in"))
      (node (ref "Y1") (pin "2") (pinfunction "2_2") (pintype "passive"))
      (node (ref "Y1") (pin "4") (pinfunction "4_4") (pintype "passive"))
      (node (ref "Y2") (pin "2") (pinfunction "2_2") (pintype "passive"))
      (node (ref "Y2") (pin "3") (pinfunction "3_3") (pintype "passive"))
    )
    (net (code "117") (name "IO_VD33") (class "Default")
      (node (ref "C19") (pin "2") (pinfunction "2_2") (pintype "passive"))
      (node (ref "C20") (pin "1") (pinfunction "1_1") (pintype "passive"))
      (node (ref "C21") (pin "2") (pinfunction "2_2") (pintype "passive"))
      (node (ref "C22") (pin "2") (pinfunction "2_2") (pintype "passive"))
      (node (ref "C23") (pin "2") (pinfunction "2_2") (pintype "passive"))
      (node (ref "C24") (pin "2") (pinfunction "2_2") (pintype "passive"))
      (node (ref "C25") (pin "2") (pinfunction "2_2") (pintype "passive"))
      (node (ref "C26") (pin "2") (pinfunction "2_2") (pintype "passive"))
      (node (ref "C27") (pin "2") (pinfunction "2_2") (pintype "passive"))
      (node (ref "FB2") (pin "2") (pinfunction "2_2") (pintype "passive"))
      (node (ref "GPIO") (pin "1") (pinfunction "1_1") (pintype "passive"))
      (node (ref "GPIO") (pin "2") (pinfunction "2_2") (pintype "passive"))
      (node (ref "R7") (pin "2") (pinfunction "2_2") (pintype "passive"))
      (node (ref "R82") (pin "2") (pinfunction "2_2") (pintype "passive"))
      (node (ref "U1") (pin "24") (pinfunction "IO_VDD_24") (pintype "power_in"))
      (node (ref "U1") (pin "57") (pinfunction "IO_VDD_57") (pintype "power_in"))
      (node (ref "U1") (pin "81") (pinfunction "IO_VDD_81") (pintype "power_in"))
      (node (ref "U1") (pin "85") (pinfunction "IO_VDD_85") (pintype "power_in"))
      (node (ref "U1") (pin "9") (pinfunction "IO_VDD_9") (pintype "power_in"))
      (node (ref "U1") (pin "98") (pinfunction "IO_VDD_98") (pintype "power_in"))
    )
    (net (code "118") (name "Net-(C2-Pad2)") (class "Default")
      (node (ref "C2") (pin "2") (pinfunction "2_2") (pintype "passive"))
      (node (ref "R1") (pin "2") (pinfunction "2_2") (pintype "passive"))
      (node (ref "R2") (pin "1") (pinfunction "1_1") (pintype "passive"))
      (node (ref "Y1") (pin "1") (pinfunction "1_1") (pintype "passive"))
    )
    (net (code "119") (name "Net-(NET-Pad1)") (class "Default")
      (node (ref "NET") (pin "1") (pinfunction "1_1") (pintype "passive"))
      (node (ref "R7") (pin "1") (pinfunction "1_1") (pintype "passive"))
    )
    (net (code "120") (name "Net-(R82-Pad1)") (class "Default")
      (node (ref "R82") (pin "1") (pinfunction "1_1") (pintype "passive"))
      (node (ref "SYS") (pin "1") (pinfunction "1_1") (pintype "passive"))
    )
    (net (code "121") (name "Net-(U1-USB0_REXT)") (class "Default")
      (node (ref "R3") (pin "1") (pinfunction "1_1") (pintype "passive"))
      (node (ref "U1") (pin "127") (pinfunction "USB0_REXT_127") (pintype "output"))
    )
    (net (code "122") (name "Net-(U1-USB1_REXT)") (class "Default")
      (node (ref "R4") (pin "1") (pinfunction "1_1") (pintype "passive"))
      (node (ref "U1") (pin "121") (pinfunction "USB1_REXT_121") (pintype "output"))
    )
    (net (code "123") (name "PLL_VD12") (class "Default")
      (node (ref "C13") (pin "2") (pinfunction "2_2") (pintype "passive"))
      (node (ref "C14") (pin "2") (pinfunction "2_2") (pintype "passive"))
      (node (ref "C15") (pin "1") (pinfunction "1_1") (pintype "passive"))
      (node (ref "FB1") (pin "2") (pinfunction "2_2") (pintype "passive"))
      (node (ref "U1") (pin "117") (pinfunction "USBPLL1_VDD_117") (pintype "power_in"))
      (node (ref "U1") (pin "122") (pinfunction "USBPLL0_VDD_122") (pintype "input"))
    )
    (net (code "124") (name "PLL_VSS") (class "Default")
      (node (ref "C13") (pin "1") (pinfunction "1_1") (pintype "passive"))
      (node (ref "C14") (pin "1") (pinfunction "1_1") (pintype "passive"))
      (node (ref "C15") (pin "2") (pinfunction "2_2") (pintype "passive"))
      (node (ref "FB3") (pin "2") (pinfunction "2_2") (pintype "passive"))
      (node (ref "U1") (pin "95") (pinfunction "PLL_VSS_95") (pintype "power_in"))
    )
    (net (code "125") (name "RTC_VD33") (class "Default")
      (node (ref "C11") (pin "1") (pinfunction "1_1") (pintype "passive"))
      (node (ref "C12") (pin "2") (pinfunction "2_2") (pintype "passive"))
      (node (ref "U1") (pin "35") (pinfunction "RTC_VDD_35") (pintype "power_in"))
    )
    (net (code "126") (name "USB0_VSS") (class "Default")
      (node (ref "C16") (pin "2") (pinfunction "2_2") (pintype "passive"))
      (node (ref "C17") (pin "1") (pinfunction "1_1") (pintype "passive"))
      (node (ref "C18") (pin "1") (pinfunction "1_1") (pintype "passive"))
      (node (ref "FB4") (pin "1") (pinfunction "1_1") (pintype "passive"))
      (node (ref "U1") (pin "123") (pinfunction "USB0_VSS_123") (pintype "power_in"))
    )
    (net (code "127") (name "USB_VD33") (class "Default")
      (node (ref "C16") (pin "1") (pinfunction "1_1") (pintype "passive"))
      (node (ref "C17") (pin "2") (pinfunction "2_2") (pintype "passive"))
      (node (ref "C18") (pin "2") (pinfunction "2_2") (pintype "passive"))
      (node (ref "FB2") (pin "1") (pinfunction "1_1") (pintype "passive"))
      (node (ref "U1") (pin "120") (pinfunction "USB1_VDD_120") (pintype "power_in"))
      (node (ref "U1") (pin "126") (pinfunction "USB0_VDD_126") (pintype "power_in"))
    )
  )
)
